# main_ver1_0.net
KiCad netlist of a schematic drawn in EAGLE
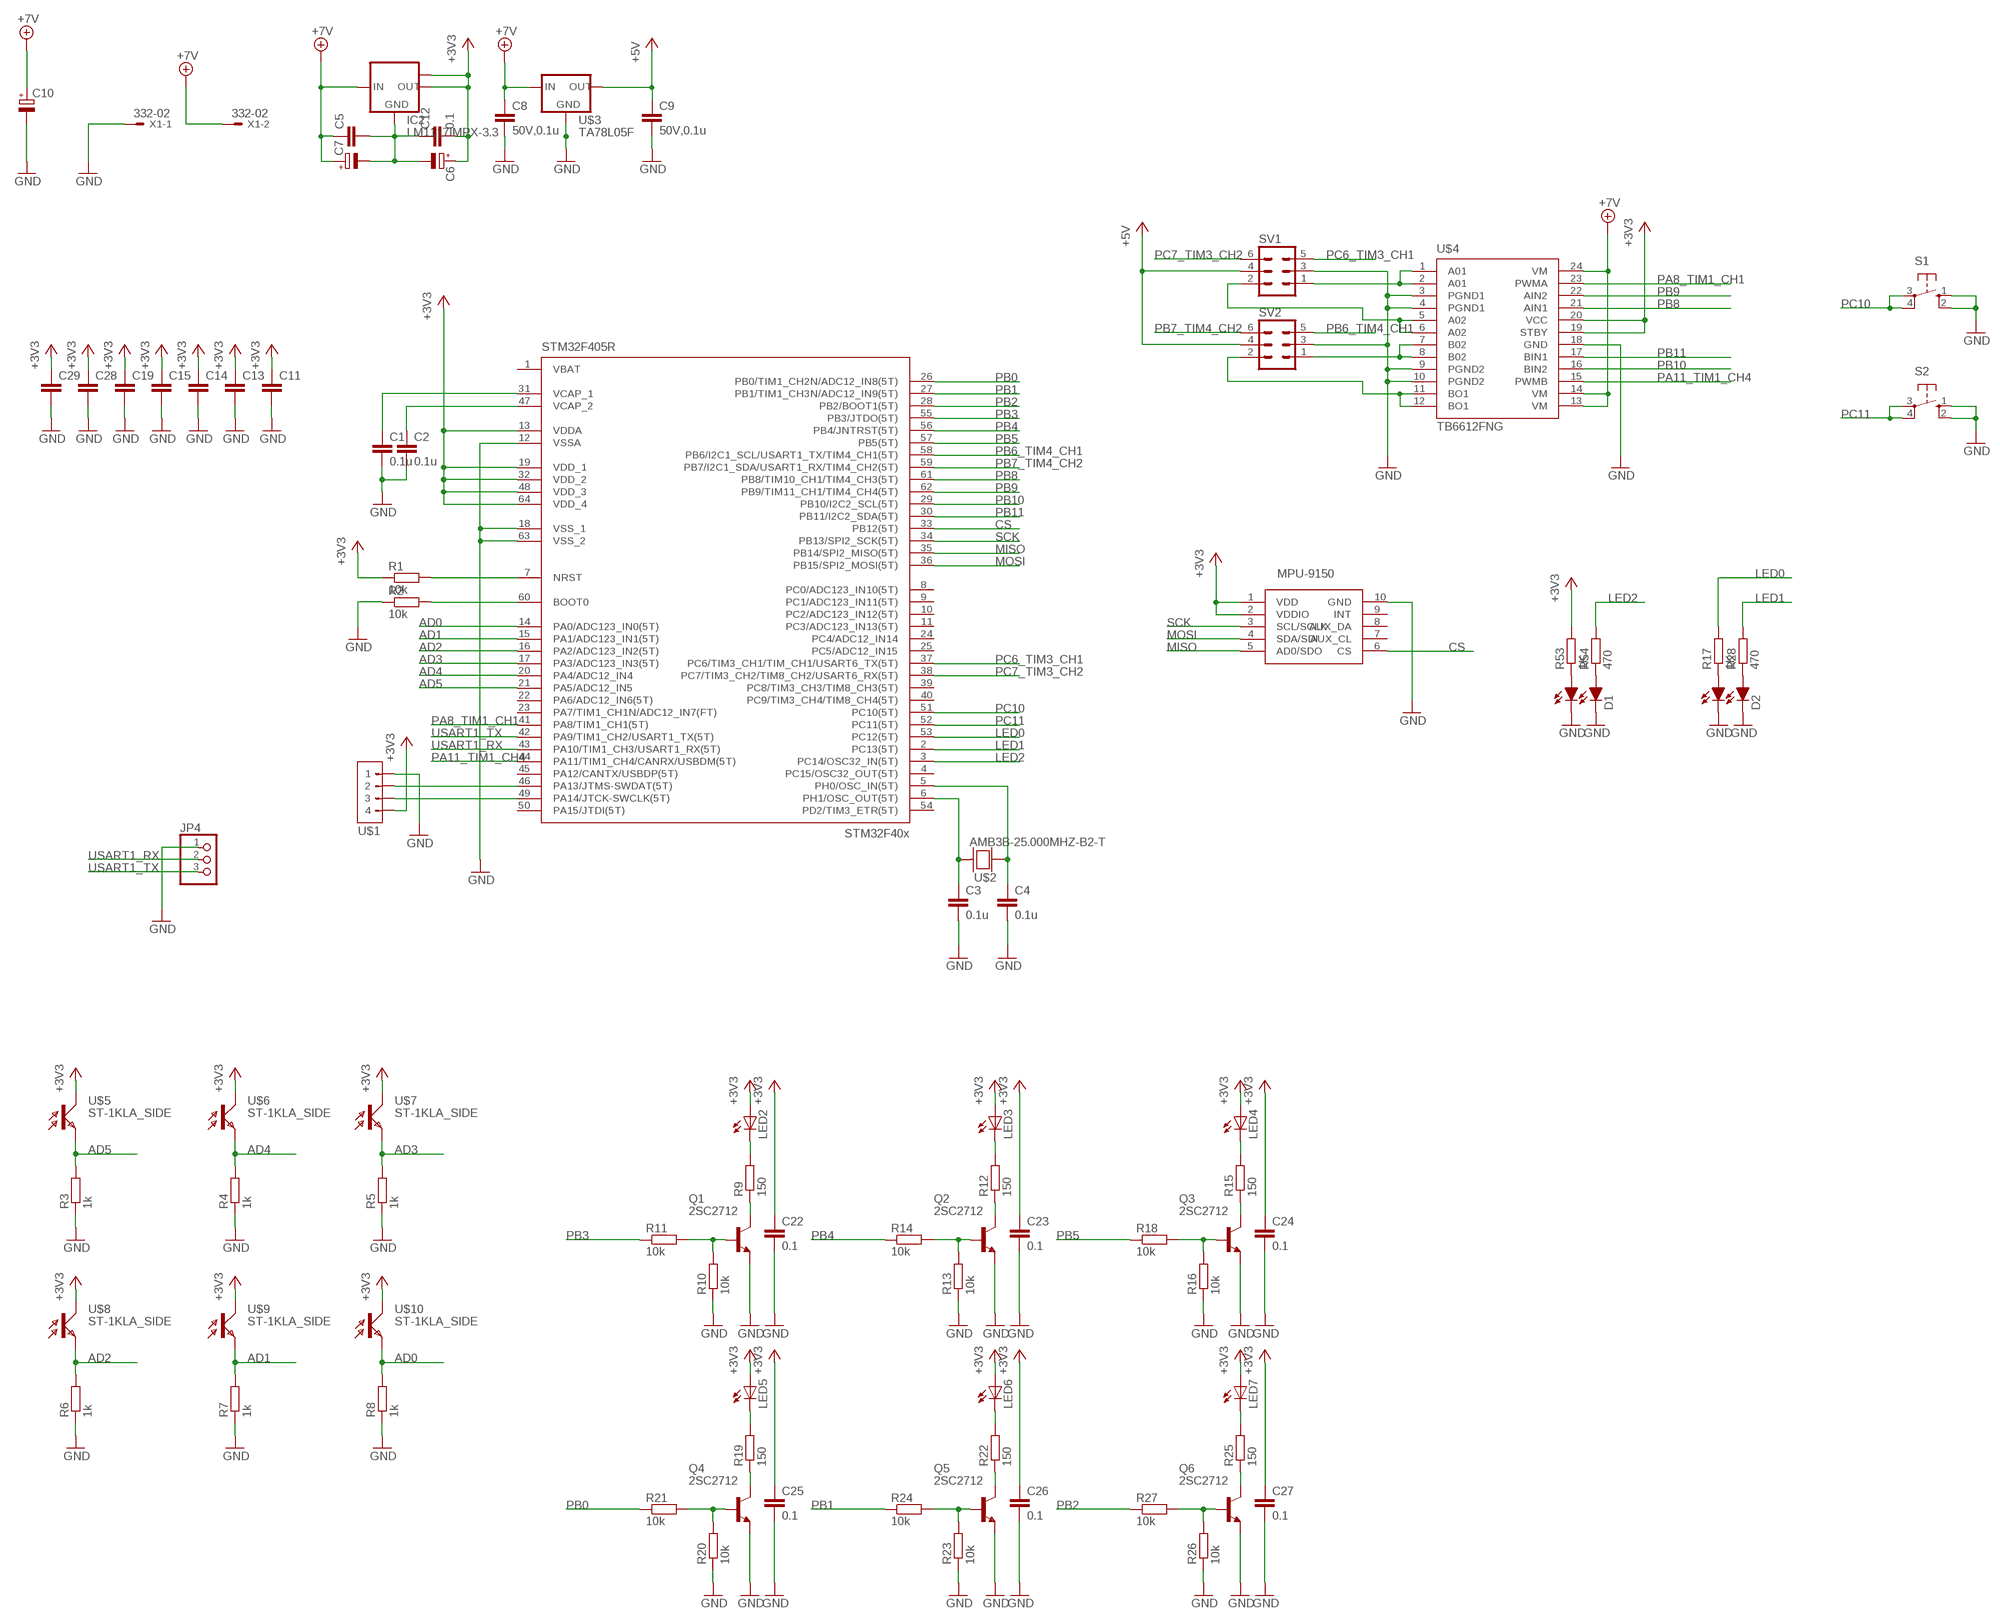
[diagram p0: schematic, sheet 1]

(export (version "E")
  (design (tool "Eeschema 10.0.6"))
  (components
    (comp (ref "C1")
      (value "0.1u")
      (footprint "eagle-import:C0603K")
      (libsource (lib "eagle-import") (part "C-EUC0603K"))
    )
    (comp (ref "C2")
      (value "0.1u")
      (footprint "eagle-import:C0603K")
      (libsource (lib "eagle-import") (part "C-EUC0603K"))
    )
    (comp (ref "C3")
      (value "0.1u")
      (footprint "eagle-import:C0603K")
      (libsource (lib "eagle-import") (part "C-EUC0603K"))
    )
    (comp (ref "C4")
      (value "0.1u")
      (footprint "eagle-import:C0603K")
      (libsource (lib "eagle-import") (part "C-EUC0603K"))
    )
    (comp (ref "C5")
      (value "C-EUC0603")
      (footprint "eagle-import:C0603")
      (libsource (lib "eagle-import") (part "C-EUC0603"))
    )
    (comp (ref "C6")
      (value "CPOL-EUSANYO_SMD_A5")
      (footprint "eagle-import:SANYO-OSCON_SMD_A5")
      (libsource (lib "eagle-import") (part "CPOL-EUSANYO_SMD_A5"))
    )
    (comp (ref "C7")
      (value "CPOL-EUSANYO_SMD_A5")
      (footprint "eagle-import:SANYO-OSCON_SMD_A5")
      (libsource (lib "eagle-import") (part "CPOL-EUSANYO_SMD_A5"))
    )
    (comp (ref "C8")
      (value "50V,0.1u")
      (footprint "eagle-import:C0603K")
      (libsource (lib "eagle-import") (part "C-EUC0603K"))
    )
    (comp (ref "C9")
      (value "50V,0.1u")
      (footprint "eagle-import:C0603K")
      (libsource (lib "eagle-import") (part "C-EUC0603K"))
    )
    (comp (ref "C10")
      (value "CPOL-EUSANYO_SMD_A5")
      (footprint "eagle-import:SANYO-OSCON_SMD_A5")
      (libsource (lib "eagle-import") (part "CPOL-EUSANYO_SMD_A5"))
    )
    (comp (ref "C11")
      (value "C-EUC0603K")
      (footprint "eagle-import:C0603K")
      (libsource (lib "eagle-import") (part "C-EUC0603K"))
    )
    (comp (ref "C12")
      (value "0.1")
      (footprint "eagle-import:C0603")
      (libsource (lib "eagle-import") (part "C-EUC0603"))
    )
    (comp (ref "C13")
      (value "C-EUC0603K")
      (footprint "eagle-import:C0603K")
      (libsource (lib "eagle-import") (part "C-EUC0603K"))
    )
    (comp (ref "C14")
      (value "C-EUC0603K")
      (footprint "eagle-import:C0603K")
      (libsource (lib "eagle-import") (part "C-EUC0603K"))
    )
    (comp (ref "C15")
      (value "C-EUC0603K")
      (footprint "eagle-import:C0603K")
      (libsource (lib "eagle-import") (part "C-EUC0603K"))
    )
    (comp (ref "C19")
      (value "C-EUC0603K")
      (footprint "eagle-import:C0603K")
      (libsource (lib "eagle-import") (part "C-EUC0603K"))
    )
    (comp (ref "C22")
      (value "0.1")
      (footprint "eagle-import:C0603")
      (libsource (lib "eagle-import") (part "C-EUC0603"))
    )
    (comp (ref "C23")
      (value "0.1")
      (footprint "eagle-import:C0603")
      (libsource (lib "eagle-import") (part "C-EUC0603"))
    )
    (comp (ref "C24")
      (value "0.1")
      (footprint "eagle-import:C0603")
      (libsource (lib "eagle-import") (part "C-EUC0603"))
    )
    (comp (ref "C25")
      (value "0.1")
      (footprint "eagle-import:C0603")
      (libsource (lib "eagle-import") (part "C-EUC0603"))
    )
    (comp (ref "C26")
      (value "0.1")
      (footprint "eagle-import:C0603")
      (libsource (lib "eagle-import") (part "C-EUC0603"))
    )
    (comp (ref "C27")
      (value "0.1")
      (footprint "eagle-import:C0603")
      (libsource (lib "eagle-import") (part "C-EUC0603"))
    )
    (comp (ref "C28")
      (value "C-EUC0603K")
      (footprint "eagle-import:C0603K")
      (libsource (lib "eagle-import") (part "C-EUC0603K"))
    )
    (comp (ref "C29")
      (value "C-EUC0603K")
      (footprint "eagle-import:C0603K")
      (libsource (lib "eagle-import") (part "C-EUC0603K"))
    )
    (comp (ref "D1")
      (value "SEC2XX4")
      (footprint "eagle-import:LED3025")
      (libsource (lib "eagle-import") (part "SEC2XX4"))
    )
    (comp (ref "D2")
      (value "SEC2XX4")
      (footprint "eagle-import:LED3025")
      (libsource (lib "eagle-import") (part "SEC2XX4"))
    )
    (comp (ref "IC2")
      (value "LM1117IMPX-3.3")
      (footprint "eagle-import:SOT223")
      (libsource (lib "eagle-import") (part "LM1117IMPX-3.3"))
    )
    (comp (ref "JP4")
      (value "PINHD-1X3/90")
      (footprint "eagle-import:1X03_90")
      (libsource (lib "eagle-import") (part "PINHD-1X3/90"))
    )
    (comp (ref "LED2")
      (value "LEDSFH480")
      (footprint "eagle-import:SFH480")
      (libsource (lib "eagle-import") (part "LEDSFH480"))
    )
    (comp (ref "LED3")
      (value "LEDSFH480")
      (footprint "eagle-import:SFH480")
      (libsource (lib "eagle-import") (part "LEDSFH480"))
    )
    (comp (ref "LED4")
      (value "LEDSFH480")
      (footprint "eagle-import:SFH480")
      (libsource (lib "eagle-import") (part "LEDSFH480"))
    )
    (comp (ref "LED5")
      (value "LEDSFH480")
      (footprint "eagle-import:SFH480")
      (libsource (lib "eagle-import") (part "LEDSFH480"))
    )
    (comp (ref "LED6")
      (value "LEDSFH480")
      (footprint "eagle-import:SFH480")
      (libsource (lib "eagle-import") (part "LEDSFH480"))
    )
    (comp (ref "LED7")
      (value "LEDSFH480")
      (footprint "eagle-import:SFH480")
      (libsource (lib "eagle-import") (part "LEDSFH480"))
    )
    (comp (ref "MPU-9250")
      (value "MPU-9250")
      (footprint "eagle-import:MPU-9250")
      (libsource (lib "eagle-import") (part "MPU-9250"))
    )
    (comp (ref "Q1")
      (value "2SC2712")
      (footprint "eagle-import:SC-59(TYPE1)")
      (libsource (lib "eagle-import") (part "2SC2712"))
    )
    (comp (ref "Q2")
      (value "2SC2712")
      (footprint "eagle-import:SC-59(TYPE1)")
      (libsource (lib "eagle-import") (part "2SC2712"))
    )
    (comp (ref "Q3")
      (value "2SC2712")
      (footprint "eagle-import:SC-59(TYPE1)")
      (libsource (lib "eagle-import") (part "2SC2712"))
    )
    (comp (ref "Q4")
      (value "2SC2712")
      (footprint "eagle-import:SC-59(TYPE1)")
      (libsource (lib "eagle-import") (part "2SC2712"))
    )
    (comp (ref "Q5")
      (value "2SC2712")
      (footprint "eagle-import:SC-59(TYPE1)")
      (libsource (lib "eagle-import") (part "2SC2712"))
    )
    (comp (ref "Q6")
      (value "2SC2712")
      (footprint "eagle-import:SC-59(TYPE1)")
      (libsource (lib "eagle-import") (part "2SC2712"))
    )
    (comp (ref "R1")
      (value "10k")
      (footprint "eagle-import:R0603")
      (libsource (lib "eagle-import") (part "R-EU_R0603"))
    )
    (comp (ref "R2")
      (value "10k")
      (footprint "eagle-import:R0603")
      (libsource (lib "eagle-import") (part "R-EU_R0603"))
    )
    (comp (ref "R3")
      (value "1k")
      (footprint "eagle-import:R0603")
      (libsource (lib "eagle-import") (part "R-EU_R0603"))
    )
    (comp (ref "R4")
      (value "1k")
      (footprint "eagle-import:R0603")
      (libsource (lib "eagle-import") (part "R-EU_R0603"))
    )
    (comp (ref "R5")
      (value "1k")
      (footprint "eagle-import:R0603")
      (libsource (lib "eagle-import") (part "R-EU_R0603"))
    )
    (comp (ref "R6")
      (value "1k")
      (footprint "eagle-import:R0603")
      (libsource (lib "eagle-import") (part "R-EU_R0603"))
    )
    (comp (ref "R7")
      (value "1k")
      (footprint "eagle-import:R0603")
      (libsource (lib "eagle-import") (part "R-EU_R0603"))
    )
    (comp (ref "R8")
      (value "1k")
      (footprint "eagle-import:R0603")
      (libsource (lib "eagle-import") (part "R-EU_R0603"))
    )
    (comp (ref "R9")
      (value "150")
      (footprint "eagle-import:R0603")
      (libsource (lib "eagle-import") (part "R-EU_R0603"))
    )
    (comp (ref "R10")
      (value "10k")
      (footprint "eagle-import:R0603")
      (libsource (lib "eagle-import") (part "R-EU_R0603"))
    )
    (comp (ref "R11")
      (value "10k")
      (footprint "eagle-import:R0603")
      (libsource (lib "eagle-import") (part "R-EU_R0603"))
    )
    (comp (ref "R12")
      (value "150")
      (footprint "eagle-import:R0603")
      (libsource (lib "eagle-import") (part "R-EU_R0603"))
    )
    (comp (ref "R13")
      (value "10k")
      (footprint "eagle-import:R0603")
      (libsource (lib "eagle-import") (part "R-EU_R0603"))
    )
    (comp (ref "R14")
      (value "10k")
      (footprint "eagle-import:R0603")
      (libsource (lib "eagle-import") (part "R-EU_R0603"))
    )
    (comp (ref "R15")
      (value "150")
      (footprint "eagle-import:R0603")
      (libsource (lib "eagle-import") (part "R-EU_R0603"))
    )
    (comp (ref "R16")
      (value "10k")
      (footprint "eagle-import:R0603")
      (libsource (lib "eagle-import") (part "R-EU_R0603"))
    )
    (comp (ref "R17")
      (value "1K")
      (footprint "eagle-import:R0603")
      (libsource (lib "eagle-import") (part "R-EU_R0603"))
    )
    (comp (ref "R18")
      (value "10k")
      (footprint "eagle-import:R0603")
      (libsource (lib "eagle-import") (part "R-EU_R0603"))
    )
    (comp (ref "R19")
      (value "150")
      (footprint "eagle-import:R0603")
      (libsource (lib "eagle-import") (part "R-EU_R0603"))
    )
    (comp (ref "R20")
      (value "10k")
      (footprint "eagle-import:R0603")
      (libsource (lib "eagle-import") (part "R-EU_R0603"))
    )
    (comp (ref "R21")
      (value "10k")
      (footprint "eagle-import:R0603")
      (libsource (lib "eagle-import") (part "R-EU_R0603"))
    )
    (comp (ref "R22")
      (value "150")
      (footprint "eagle-import:R0603")
      (libsource (lib "eagle-import") (part "R-EU_R0603"))
    )
    (comp (ref "R23")
      (value "10k")
      (footprint "eagle-import:R0603")
      (libsource (lib "eagle-import") (part "R-EU_R0603"))
    )
    (comp (ref "R24")
      (value "10k")
      (footprint "eagle-import:R0603")
      (libsource (lib "eagle-import") (part "R-EU_R0603"))
    )
    (comp (ref "R25")
      (value "150")
      (footprint "eagle-import:R0603")
      (libsource (lib "eagle-import") (part "R-EU_R0603"))
    )
    (comp (ref "R26")
      (value "10k")
      (footprint "eagle-import:R0603")
      (libsource (lib "eagle-import") (part "R-EU_R0603"))
    )
    (comp (ref "R27")
      (value "10k")
      (footprint "eagle-import:R0603")
      (libsource (lib "eagle-import") (part "R-EU_R0603"))
    )
    (comp (ref "R28")
      (value "470")
      (footprint "eagle-import:R0603")
      (libsource (lib "eagle-import") (part "R-EU_R0603"))
    )
    (comp (ref "R53")
      (value "1K")
      (footprint "eagle-import:R0603")
      (libsource (lib "eagle-import") (part "R-EU_R0603"))
    )
    (comp (ref "R54")
      (value "470")
      (footprint "eagle-import:R0603")
      (libsource (lib "eagle-import") (part "R-EU_R0603"))
    )
    (comp (ref "S1")
      (value "10-XX")
      (footprint "eagle-import:B3F-10XX")
      (fields (field (name "MPN") "B3F-1000"))
      (libsource (lib "eagle-import") (part "10-XX"))
    )
    (comp (ref "S2")
      (value "10-XX")
      (footprint "eagle-import:B3F-10XX")
      (fields (field (name "MPN") "B3F-1000"))
      (libsource (lib "eagle-import") (part "10-XX"))
    )
    (comp (ref "STM32F405R")
      (value "STM32F405R")
      (footprint "eagle-import:TQFP64")
      (libsource (lib "eagle-import") (part "STM32F405R"))
    )
    (comp (ref "SV1")
      (value "ML6")
      (footprint "eagle-import:ML6")
      (libsource (lib "eagle-import") (part "ML6"))
    )
    (comp (ref "SV2")
      (value "ML6")
      (footprint "eagle-import:ML6")
      (libsource (lib "eagle-import") (part "ML6"))
    )
    (comp (ref "U$1")
      (value "TOP_TYPE_4PIN")
      (footprint "eagle-import:TOP_TYPE_4PIN")
      (libsource (lib "eagle-import") (part "TOP_TYPE_4PIN"))
    )
    (comp (ref "U$2")
      (value "AMB3B-25.000MHZ-B2-T")
      (footprint "eagle-import:4LCC")
      (libsource (lib "eagle-import") (part "AMB3B-25.000MHZ-B2-T"))
    )
    (comp (ref "U$3")
      (value "TA78L05F")
      (footprint "eagle-import:SOT89")
      (libsource (lib "eagle-import") (part "TA78L05F"))
    )
    (comp (ref "U$4")
      (value "TB6612FNG")
      (footprint "eagle-import:SSOP24")
      (libsource (lib "eagle-import") (part "TB6612FNG"))
    )
    (comp (ref "U$5")
      (value "ST-1KLA_SIDE")
      (footprint "eagle-import:TO18-SIDE")
      (libsource (lib "eagle-import") (part "ST-1KLA_SIDE"))
    )
    (comp (ref "U$6")
      (value "ST-1KLA_SIDE")
      (footprint "eagle-import:TO18-SIDE")
      (libsource (lib "eagle-import") (part "ST-1KLA_SIDE"))
    )
    (comp (ref "U$7")
      (value "ST-1KLA_SIDE")
      (footprint "eagle-import:TO18-SIDE")
      (libsource (lib "eagle-import") (part "ST-1KLA_SIDE"))
    )
    (comp (ref "U$8")
      (value "ST-1KLA_SIDE")
      (footprint "eagle-import:TO18-SIDE")
      (libsource (lib "eagle-import") (part "ST-1KLA_SIDE"))
    )
    (comp (ref "U$9")
      (value "ST-1KLA_SIDE")
      (footprint "eagle-import:TO18-SIDE")
      (libsource (lib "eagle-import") (part "ST-1KLA_SIDE"))
    )
    (comp (ref "U$10")
      (value "ST-1KLA_SIDE")
      (footprint "eagle-import:TO18-SIDE")
      (libsource (lib "eagle-import") (part "ST-1KLA_SIDE"))
    )
    (comp (ref "X1")
      (value "332-02")
      (footprint "eagle-import:332-02")
      (libsource (lib "eagle-import") (part "332-02"))
    )
  )
  (nets
    (net (code "1") (name "+3V3") (class "Default")
      (node (ref "C11") (pin "1") (pinfunction "1_1") (pintype "passive"))
      (node (ref "C12") (pin "2") (pinfunction "2_2") (pintype "passive"))
      (node (ref "C13") (pin "1") (pinfunction "1_1") (pintype "passive"))
      (node (ref "C14") (pin "1") (pinfunction "1_1") (pintype "passive"))
      (node (ref "C15") (pin "1") (pinfunction "1_1") (pintype "passive"))
      (node (ref "C19") (pin "1") (pinfunction "1_1") (pintype "passive"))
      (node (ref "C22") (pin "1") (pinfunction "1_1") (pintype "passive"))
      (node (ref "C23") (pin "1") (pinfunction "1_1") (pintype "passive"))
      (node (ref "C24") (pin "1") (pinfunction "1_1") (pintype "passive"))
      (node (ref "C25") (pin "1") (pinfunction "1_1") (pintype "passive"))
      (node (ref "C26") (pin "1") (pinfunction "1_1") (pintype "passive"))
      (node (ref "C27") (pin "1") (pinfunction "1_1") (pintype "passive"))
      (node (ref "C28") (pin "1") (pinfunction "1_1") (pintype "passive"))
      (node (ref "C29") (pin "1") (pinfunction "1_1") (pintype "passive"))
      (node (ref "C6") (pin "+") (pinfunction "+_+") (pintype "passive"))
      (node (ref "IC2") (pin "2") (pinfunction "OUT_2") (pintype "passive"))
      (node (ref "IC2") (pin "TAB") (pinfunction "OUT1_TAB") (pintype "passive"))
      (node (ref "LED2") (pin "A") (pinfunction "A_A") (pintype "passive"))
      (node (ref "LED3") (pin "A") (pinfunction "A_A") (pintype "passive"))
      (node (ref "LED4") (pin "A") (pinfunction "A_A") (pintype "passive"))
      (node (ref "LED5") (pin "A") (pinfunction "A_A") (pintype "passive"))
      (node (ref "LED6") (pin "A") (pinfunction "A_A") (pintype "passive"))
      (node (ref "LED7") (pin "A") (pinfunction "A_A") (pintype "passive"))
      (node (ref "MPU-9250") (pin "1") (pinfunction "VDD_1") (pintype "bidirectional"))
      (node (ref "MPU-9250") (pin "2") (pinfunction "VDDIO_2") (pintype "bidirectional"))
      (node (ref "R1") (pin "1") (pinfunction "1_1") (pintype "passive"))
      (node (ref "R53") (pin "2") (pinfunction "2_2") (pintype "passive"))
      (node (ref "STM32F405R") (pin "13") (pinfunction "VDDA_13") (pintype "bidirectional"))
      (node (ref "STM32F405R") (pin "19") (pinfunction "VDD_1_19") (pintype "bidirectional"))
      (node (ref "STM32F405R") (pin "32") (pinfunction "VDD_2_32") (pintype "bidirectional"))
      (node (ref "STM32F405R") (pin "48") (pinfunction "VDD_3_48") (pintype "bidirectional"))
      (node (ref "STM32F405R") (pin "64") (pinfunction "VDD_4_64") (pintype "bidirectional"))
      (node (ref "U$1") (pin "4") (pinfunction "4_4") (pintype "passive"))
      (node (ref "U$10") (pin "P$2") (pinfunction "C_P$2") (pintype "passive"))
      (node (ref "U$4") (pin "19") (pinfunction "STBY_19") (pintype "bidirectional"))
      (node (ref "U$4") (pin "20") (pinfunction "VCC_20") (pintype "bidirectional"))
      (node (ref "U$5") (pin "P$2") (pinfunction "C_P$2") (pintype "passive"))
      (node (ref "U$6") (pin "P$2") (pinfunction "C_P$2") (pintype "passive"))
      (node (ref "U$7") (pin "P$2") (pinfunction "C_P$2") (pintype "passive"))
      (node (ref "U$8") (pin "P$2") (pinfunction "C_P$2") (pintype "passive"))
      (node (ref "U$9") (pin "P$2") (pinfunction "C_P$2") (pintype "passive"))
    )
    (net (code "2") (name "+5V") (class "Default")
      (node (ref "C9") (pin "1") (pinfunction "1_1") (pintype "passive"))
      (node (ref "SV1") (pin "4") (pinfunction "4_4") (pintype "passive"))
      (node (ref "SV2") (pin "4") (pinfunction "4_4") (pintype "passive"))
      (node (ref "U$3") (pin "1") (pinfunction "OUT_1") (pintype "passive"))
    )
    (net (code "3") (name "+7V") (class "Default")
      (node (ref "C10") (pin "+") (pinfunction "+_+") (pintype "passive"))
      (node (ref "C5") (pin "1") (pinfunction "1_1") (pintype "passive"))
      (node (ref "C7") (pin "+") (pinfunction "+_+") (pintype "passive"))
      (node (ref "C8") (pin "1") (pinfunction "1_1") (pintype "passive"))
      (node (ref "IC2") (pin "3") (pinfunction "IN_3") (pintype "input"))
      (node (ref "U$3") (pin "3") (pinfunction "IN_3") (pintype "input"))
      (node (ref "U$4") (pin "13") (pinfunction "VM_13") (pintype "bidirectional"))
      (node (ref "U$4") (pin "14") (pinfunction "VM_14") (pintype "bidirectional"))
      (node (ref "U$4") (pin "24") (pinfunction "VM_24") (pintype "bidirectional"))
      (node (ref "X1") (pin "2") (pinfunction "S_2") (pintype "passive"))
    )
    (net (code "4") (name "/AD0") (class "Default")
      (node (ref "R8") (pin "2") (pinfunction "2_2") (pintype "passive"))
      (node (ref "STM32F405R") (pin "14") (pinfunction "PA0/ADC123_IN0(5T)_14") (pintype "bidirectional"))
      (node (ref "U$10") (pin "P$1") (pinfunction "E_P$1") (pintype "passive"))
    )
    (net (code "5") (name "/AD1") (class "Default")
      (node (ref "R7") (pin "2") (pinfunction "2_2") (pintype "passive"))
      (node (ref "STM32F405R") (pin "15") (pinfunction "PA1/ADC123_IN1(5T)_15") (pintype "bidirectional"))
      (node (ref "U$9") (pin "P$1") (pinfunction "E_P$1") (pintype "passive"))
    )
    (net (code "6") (name "/AD2") (class "Default")
      (node (ref "R6") (pin "2") (pinfunction "2_2") (pintype "passive"))
      (node (ref "STM32F405R") (pin "16") (pinfunction "PA2/ADC123_IN2(5T)_16") (pintype "bidirectional"))
      (node (ref "U$8") (pin "P$1") (pinfunction "E_P$1") (pintype "passive"))
    )
    (net (code "7") (name "/AD3") (class "Default")
      (node (ref "R5") (pin "2") (pinfunction "2_2") (pintype "passive"))
      (node (ref "STM32F405R") (pin "17") (pinfunction "PA3/ADC123_IN3(5T)_17") (pintype "bidirectional"))
      (node (ref "U$7") (pin "P$1") (pinfunction "E_P$1") (pintype "passive"))
    )
    (net (code "8") (name "/AD4") (class "Default")
      (node (ref "R4") (pin "2") (pinfunction "2_2") (pintype "passive"))
      (node (ref "STM32F405R") (pin "20") (pinfunction "PA4/ADC12_IN4_20") (pintype "bidirectional"))
      (node (ref "U$6") (pin "P$1") (pinfunction "E_P$1") (pintype "passive"))
    )
    (net (code "9") (name "/AD5") (class "Default")
      (node (ref "R3") (pin "2") (pinfunction "2_2") (pintype "passive"))
      (node (ref "STM32F405R") (pin "21") (pinfunction "PA5/ADC12_IN5_21") (pintype "bidirectional"))
      (node (ref "U$5") (pin "P$1") (pinfunction "E_P$1") (pintype "passive"))
    )
    (net (code "10") (name "/CS") (class "Default")
      (node (ref "MPU-9250") (pin "6") (pinfunction "CS_6") (pintype "bidirectional"))
      (node (ref "STM32F405R") (pin "33") (pinfunction "PB12(5T)_33") (pintype "bidirectional"))
    )
    (net (code "11") (name "/LED0") (class "Default")
      (node (ref "R17") (pin "2") (pinfunction "2_2") (pintype "passive"))
      (node (ref "STM32F405R") (pin "53") (pinfunction "PC12(5T)_53") (pintype "bidirectional"))
    )
    (net (code "12") (name "/LED1") (class "Default")
      (node (ref "R28") (pin "2") (pinfunction "2_2") (pintype "passive"))
      (node (ref "STM32F405R") (pin "2") (pinfunction "PC13(5T)_2") (pintype "bidirectional"))
    )
    (net (code "13") (name "/LED2") (class "Default")
      (node (ref "R54") (pin "2") (pinfunction "2_2") (pintype "passive"))
      (node (ref "STM32F405R") (pin "3") (pinfunction "PC14/OSC32_IN(5T)_3") (pintype "bidirectional"))
    )
    (net (code "14") (name "/MISO") (class "Default")
      (node (ref "MPU-9250") (pin "5") (pinfunction "AD0/SDO_5") (pintype "bidirectional"))
      (node (ref "STM32F405R") (pin "35") (pinfunction "PB14/SPI2_MISO(5T)_35") (pintype "bidirectional"))
    )
    (net (code "15") (name "/MOSI") (class "Default")
      (node (ref "MPU-9250") (pin "4") (pinfunction "SDA/SDI_4") (pintype "bidirectional"))
      (node (ref "STM32F405R") (pin "36") (pinfunction "PB15/SPI2_MOSI(5T)_36") (pintype "bidirectional"))
    )
    (net (code "16") (name "/PA8_TIM1_CH1") (class "Default")
      (node (ref "STM32F405R") (pin "41") (pinfunction "PA8/TIM1_CH1(5T)_41") (pintype "bidirectional"))
      (node (ref "U$4") (pin "23") (pinfunction "PWMA_23") (pintype "bidirectional"))
    )
    (net (code "17") (name "/PA11_TIM1_CH4") (class "Default")
      (node (ref "STM32F405R") (pin "44") (pinfunction "PA11/TIM1_CH4/CANRX/USBDM(5T)_44") (pintype "bidirectional"))
      (node (ref "U$4") (pin "15") (pinfunction "PWMB_15") (pintype "bidirectional"))
    )
    (net (code "18") (name "/PB0") (class "Default")
      (node (ref "R21") (pin "1") (pinfunction "1_1") (pintype "passive"))
      (node (ref "STM32F405R") (pin "26") (pinfunction "PB0/TIM1_CH2N/ADC12_IN8(5T)_26") (pintype "bidirectional"))
    )
    (net (code "19") (name "/PB1") (class "Default")
      (node (ref "R24") (pin "1") (pinfunction "1_1") (pintype "passive"))
      (node (ref "STM32F405R") (pin "27") (pinfunction "PB1/TIM1_CH3N/ADC12_IN9(5T)_27") (pintype "bidirectional"))
    )
    (net (code "20") (name "/PB2") (class "Default")
      (node (ref "R27") (pin "1") (pinfunction "1_1") (pintype "passive"))
      (node (ref "STM32F405R") (pin "28") (pinfunction "PB2/BOOT1(5T)_28") (pintype "bidirectional"))
    )
    (net (code "21") (name "/PB3") (class "Default")
      (node (ref "R11") (pin "1") (pinfunction "1_1") (pintype "passive"))
      (node (ref "STM32F405R") (pin "55") (pinfunction "PB3/JTDO(5T)_55") (pintype "bidirectional"))
    )
    (net (code "22") (name "/PB4") (class "Default")
      (node (ref "R14") (pin "1") (pinfunction "1_1") (pintype "passive"))
      (node (ref "STM32F405R") (pin "56") (pinfunction "PB4/JNTRST(5T)_56") (pintype "bidirectional"))
    )
    (net (code "23") (name "/PB5") (class "Default")
      (node (ref "R18") (pin "1") (pinfunction "1_1") (pintype "passive"))
      (node (ref "STM32F405R") (pin "57") (pinfunction "PB5(5T)_57") (pintype "bidirectional"))
    )
    (net (code "24") (name "/PB6_TIM4_CH1") (class "Default")
      (node (ref "STM32F405R") (pin "58") (pinfunction "PB6/I2C1_SCL/USART1_TX/TIM4_CH1(5T)_58") (pintype "bidirectional"))
      (node (ref "SV2") (pin "5") (pinfunction "5_5") (pintype "passive"))
    )
    (net (code "25") (name "/PB7_TIM4_CH2") (class "Default")
      (node (ref "STM32F405R") (pin "59") (pinfunction "PB7/I2C1_SDA/USART1_RX/TIM4_CH2(5T)_59") (pintype "bidirectional"))
      (node (ref "SV2") (pin "6") (pinfunction "6_6") (pintype "passive"))
    )
    (net (code "26") (name "/PB8") (class "Default")
      (node (ref "STM32F405R") (pin "61") (pinfunction "PB8/TIM10_CH1/TIM4_CH3(5T)_61") (pintype "bidirectional"))
      (node (ref "U$4") (pin "21") (pinfunction "AIN1_21") (pintype "bidirectional"))
    )
    (net (code "27") (name "/PB9") (class "Default")
      (node (ref "STM32F405R") (pin "62") (pinfunction "PB9/TIM11_CH1/TIM4_CH4(5T)_62") (pintype "bidirectional"))
      (node (ref "U$4") (pin "22") (pinfunction "AIN2_22") (pintype "bidirectional"))
    )
    (net (code "28") (name "/PB10") (class "Default")
      (node (ref "STM32F405R") (pin "29") (pinfunction "PB10/I2C2_SCL(5T)_29") (pintype "bidirectional"))
      (node (ref "U$4") (pin "16") (pinfunction "BIN2_16") (pintype "bidirectional"))
    )
    (net (code "29") (name "/PB11") (class "Default")
      (node (ref "STM32F405R") (pin "30") (pinfunction "PB11/I2C2_SDA(5T)_30") (pintype "bidirectional"))
      (node (ref "U$4") (pin "17") (pinfunction "BIN1_17") (pintype "bidirectional"))
    )
    (net (code "30") (name "/PC6_TIM3_CH1") (class "Default")
      (node (ref "STM32F405R") (pin "37") (pinfunction "PC6/TIM3_CH1/TIM_CH1/USART6_TX(5T)_37") (pintype "bidirectional"))
      (node (ref "SV1") (pin "5") (pinfunction "5_5") (pintype "passive"))
    )
    (net (code "31") (name "/PC7_TIM3_CH2") (class "Default")
      (node (ref "STM32F405R") (pin "38") (pinfunction "PC7/TIM3_CH2/TIM8_CH2/USART6_RX(5T)_38") (pintype "bidirectional"))
      (node (ref "SV1") (pin "6") (pinfunction "6_6") (pintype "passive"))
    )
    (net (code "32") (name "/PC10") (class "Default")
      (node (ref "S1") (pin "3") (pinfunction "P_3") (pintype "passive"))
      (node (ref "S1") (pin "4") (pinfunction "P1_4") (pintype "passive"))
      (node (ref "STM32F405R") (pin "51") (pinfunction "PC10(5T)_51") (pintype "bidirectional"))
    )
    (net (code "33") (name "/PC11") (class "Default")
      (node (ref "S2") (pin "3") (pinfunction "P_3") (pintype "passive"))
      (node (ref "S2") (pin "4") (pinfunction "P1_4") (pintype "passive"))
      (node (ref "STM32F405R") (pin "52") (pinfunction "PC11(5T)_52") (pintype "bidirectional"))
    )
    (net (code "34") (name "/SCK") (class "Default")
      (node (ref "MPU-9250") (pin "3") (pinfunction "SCL/SCLK_3") (pintype "bidirectional"))
      (node (ref "STM32F405R") (pin "34") (pinfunction "PB13/SPI2_SCK(5T)_34") (pintype "bidirectional"))
    )
    (net (code "35") (name "/USART1_RX") (class "Default")
      (node (ref "JP4") (pin "2") (pinfunction "2_2") (pintype "passive"))
      (node (ref "STM32F405R") (pin "43") (pinfunction "PA10/TIM1_CH3/USART1_RX(5T)_43") (pintype "bidirectional"))
    )
    (net (code "36") (name "/USART1_TX") (class "Default")
      (node (ref "JP4") (pin "3") (pinfunction "3_3") (pintype "passive"))
      (node (ref "STM32F405R") (pin "42") (pinfunction "PA9/TIM1_CH2/USART1_TX(5T)_42") (pintype "bidirectional"))
    )
    (net (code "37") (name "GND") (class "Default")
      (node (ref "C1") (pin "2") (pinfunction "2_2") (pintype "passive"))
      (node (ref "C10") (pin "-") (pinfunction "-_-") (pintype "passive"))
      (node (ref "C11") (pin "2") (pinfunction "2_2") (pintype "passive"))
      (node (ref "C12") (pin "1") (pinfunction "1_1") (pintype "passive"))
      (node (ref "C13") (pin "2") (pinfunction "2_2") (pintype "passive"))
      (node (ref "C14") (pin "2") (pinfunction "2_2") (pintype "passive"))
      (node (ref "C15") (pin "2") (pinfunction "2_2") (pintype "passive"))
      (node (ref "C19") (pin "2") (pinfunction "2_2") (pintype "passive"))
      (node (ref "C2") (pin "2") (pinfunction "2_2") (pintype "passive"))
      (node (ref "C22") (pin "2") (pinfunction "2_2") (pintype "passive"))
      (node (ref "C23") (pin "2") (pinfunction "2_2") (pintype "passive"))
      (node (ref "C24") (pin "2") (pinfunction "2_2") (pintype "passive"))
      (node (ref "C25") (pin "2") (pinfunction "2_2") (pintype "passive"))
      (node (ref "C26") (pin "2") (pinfunction "2_2") (pintype "passive"))
      (node (ref "C27") (pin "2") (pinfunction "2_2") (pintype "passive"))
      (node (ref "C28") (pin "2") (pinfunction "2_2") (pintype "passive"))
      (node (ref "C29") (pin "2") (pinfunction "2_2") (pintype "passive"))
      (node (ref "C3") (pin "2") (pinfunction "2_2") (pintype "passive"))
      (node (ref "C4") (pin "2") (pinfunction "2_2") (pintype "passive"))
      (node (ref "C5") (pin "2") (pinfunction "2_2") (pintype "passive"))
      (node (ref "C6") (pin "-") (pinfunction "-_-") (pintype "passive"))
      (node (ref "C7") (pin "-") (pinfunction "-_-") (pintype "passive"))
      (node (ref "C8") (pin "2") (pinfunction "2_2") (pintype "passive"))
      (node (ref "C9") (pin "2") (pinfunction "2_2") (pintype "passive"))
      (node (ref "D1") (pin "1") (pinfunction "C0_1") (pintype "passive"))
      (node (ref "D1") (pin "2") (pinfunction "C1_2") (pintype "passive"))
      (node (ref "D2") (pin "1") (pinfunction "C0_1") (pintype "passive"))
      (node (ref "D2") (pin "2") (pinfunction "C1_2") (pintype "passive"))
      (node (ref "IC2") (pin "1") (pinfunction "GND_1") (pintype "input"))
      (node (ref "JP4") (pin "1") (pinfunction "1_1") (pintype "passive"))
      (node (ref "MPU-9250") (pin "10") (pinfunction "GND_10") (pintype "bidirectional"))
      (node (ref "Q1") (pin "E") (pinfunction "E_E") (pintype "passive"))
      (node (ref "Q2") (pin "E") (pinfunction "E_E") (pintype "passive"))
      (node (ref "Q3") (pin "E") (pinfunction "E_E") (pintype "passive"))
      (node (ref "Q4") (pin "E") (pinfunction "E_E") (pintype "passive"))
      (node (ref "Q5") (pin "E") (pinfunction "E_E") (pintype "passive"))
      (node (ref "Q6") (pin "E") (pinfunction "E_E") (pintype "passive"))
      (node (ref "R10") (pin "1") (pinfunction "1_1") (pintype "passive"))
      (node (ref "R13") (pin "1") (pinfunction "1_1") (pintype "passive"))
      (node (ref "R16") (pin "1") (pinfunction "1_1") (pintype "passive"))
      (node (ref "R2") (pin "1") (pinfunction "1_1") (pintype "passive"))
      (node (ref "R20") (pin "1") (pinfunction "1_1") (pintype "passive"))
      (node (ref "R23") (pin "1") (pinfunction "1_1") (pintype "passive"))
      (node (ref "R26") (pin "1") (pinfunction "1_1") (pintype "passive"))
      (node (ref "R3") (pin "1") (pinfunction "1_1") (pintype "passive"))
      (node (ref "R4") (pin "1") (pinfunction "1_1") (pintype "passive"))
      (node (ref "R5") (pin "1") (pinfunction "1_1") (pintype "passive"))
      (node (ref "R6") (pin "1") (pinfunction "1_1") (pintype "passive"))
      (node (ref "R7") (pin "1") (pinfunction "1_1") (pintype "passive"))
      (node (ref "R8") (pin "1") (pinfunction "1_1") (pintype "passive"))
      (node (ref "S1") (pin "1") (pinfunction "S_1") (pintype "passive"))
      (node (ref "S1") (pin "2") (pinfunction "S1_2") (pintype "passive"))
      (node (ref "S2") (pin "1") (pinfunction "S_1") (pintype "passive"))
      (node (ref "S2") (pin "2") (pinfunction "S1_2") (pintype "passive"))
      (node (ref "STM32F405R") (pin "12") (pinfunction "VSSA_12") (pintype "bidirectional"))
      (node (ref "STM32F405R") (pin "18") (pinfunction "VSS_1_18") (pintype "bidirectional"))
      (node (ref "STM32F405R") (pin "63") (pinfunction "VSS_2_63") (pintype "bidirectional"))
      (node (ref "SV1") (pin "3") (pinfunction "3_3") (pintype "passive"))
      (node (ref "SV2") (pin "3") (pinfunction "3_3") (pintype "passive"))
      (node (ref "U$1") (pin "1") (pinfunction "1_1") (pintype "passive"))
      (node (ref "U$3") (pin "2") (pinfunction "GND_2") (pintype "input"))
      (node (ref "U$3") (pin "2@1") (pinfunction "GND1_2@1") (pintype "input"))
      (node (ref "U$4") (pin "10") (pinfunction "PGND2_10") (pintype "bidirectional"))
      (node (ref "U$4") (pin "18") (pinfunction "GND_18") (pintype "bidirectional"))
      (node (ref "U$4") (pin "3") (pinfunction "PGND1_3") (pintype "bidirectional"))
      (node (ref "U$4") (pin "4") (pinfunction "PGND1_4") (pintype "bidirectional"))
      (node (ref "U$4") (pin "9") (pinfunction "PGND2_9") (pintype "bidirectional"))
      (node (ref "X1") (pin "1") (pinfunction "S_1") (pintype "passive"))
    )
    (net (code "38") (name "Net-(D1-A0)") (class "Default")
      (node (ref "D1") (pin "4") (pinfunction "A0_4") (pintype "passive"))
      (node (ref "R54") (pin "1") (pinfunction "1_1") (pintype "passive"))
    )
    (net (code "39") (name "Net-(D1-A1)") (class "Default")
      (node (ref "D1") (pin "3") (pinfunction "A1_3") (pintype "passive"))
      (node (ref "R53") (pin "1") (pinfunction "1_1") (pintype "passive"))
    )
    (net (code "40") (name "Net-(D2-A0)") (class "Default")
      (node (ref "D2") (pin "4") (pinfunction "A0_4") (pintype "passive"))
      (node (ref "R28") (pin "1") (pinfunction "1_1") (pintype "passive"))
    )
    (net (code "41") (name "Net-(D2-A1)") (class "Default")
      (node (ref "D2") (pin "3") (pinfunction "A1_3") (pintype "passive"))
      (node (ref "R17") (pin "1") (pinfunction "1_1") (pintype "passive"))
    )
    (net (code "42") (name "Net-(LED2-C)") (class "Default")
      (node (ref "LED2") (pin "K") (pinfunction "C_K") (pintype "passive"))
      (node (ref "R9") (pin "2") (pinfunction "2_2") (pintype "passive"))
    )
    (net (code "43") (name "Net-(LED3-C)") (class "Default")
      (node (ref "LED3") (pin "K") (pinfunction "C_K") (pintype "passive"))
      (node (ref "R12") (pin "2") (pinfunction "2_2") (pintype "passive"))
    )
    (net (code "44") (name "Net-(LED4-C)") (class "Default")
      (node (ref "LED4") (pin "K") (pinfunction "C_K") (pintype "passive"))
      (node (ref "R15") (pin "2") (pinfunction "2_2") (pintype "passive"))
    )
    (net (code "45") (name "Net-(LED5-C)") (class "Default")
      (node (ref "LED5") (pin "K") (pinfunction "C_K") (pintype "passive"))
      (node (ref "R19") (pin "2") (pinfunction "2_2") (pintype "passive"))
    )
    (net (code "46") (name "Net-(LED6-C)") (class "Default")
      (node (ref "LED6") (pin "K") (pinfunction "C_K") (pintype "passive"))
      (node (ref "R22") (pin "2") (pinfunction "2_2") (pintype "passive"))
    )
    (net (code "47") (name "Net-(LED7-C)") (class "Default")
      (node (ref "LED7") (pin "K") (pinfunction "C_K") (pintype "passive"))
      (node (ref "R25") (pin "2") (pinfunction "2_2") (pintype "passive"))
    )
    (net (code "48") (name "Net-(Q1-PadB)") (class "Default")
      (node (ref "Q1") (pin "B") (pinfunction "B_B") (pintype "passive"))
      (node (ref "R10") (pin "2") (pinfunction "2_2") (pintype "passive"))
      (node (ref "R11") (pin "2") (pinfunction "2_2") (pintype "passive"))
    )
    (net (code "49") (name "Net-(Q1-PadC)") (class "Default")
      (node (ref "Q1") (pin "C") (pinfunction "C_C") (pintype "passive"))
      (node (ref "R9") (pin "1") (pinfunction "1_1") (pintype "passive"))
    )
    (net (code "50") (name "Net-(Q2-PadB)") (class "Default")
      (node (ref "Q2") (pin "B") (pinfunction "B_B") (pintype "passive"))
      (node (ref "R13") (pin "2") (pinfunction "2_2") (pintype "passive"))
      (node (ref "R14") (pin "2") (pinfunction "2_2") (pintype "passive"))
    )
    (net (code "51") (name "Net-(Q2-PadC)") (class "Default")
      (node (ref "Q2") (pin "C") (pinfunction "C_C") (pintype "passive"))
      (node (ref "R12") (pin "1") (pinfunction "1_1") (pintype "passive"))
    )
    (net (code "52") (name "Net-(Q3-PadB)") (class "Default")
      (node (ref "Q3") (pin "B") (pinfunction "B_B") (pintype "passive"))
      (node (ref "R16") (pin "2") (pinfunction "2_2") (pintype "passive"))
      (node (ref "R18") (pin "2") (pinfunction "2_2") (pintype "passive"))
    )
    (net (code "53") (name "Net-(Q3-PadC)") (class "Default")
      (node (ref "Q3") (pin "C") (pinfunction "C_C") (pintype "passive"))
      (node (ref "R15") (pin "1") (pinfunction "1_1") (pintype "passive"))
    )
    (net (code "54") (name "Net-(Q4-PadB)") (class "Default")
      (node (ref "Q4") (pin "B") (pinfunction "B_B") (pintype "passive"))
      (node (ref "R20") (pin "2") (pinfunction "2_2") (pintype "passive"))
      (node (ref "R21") (pin "2") (pinfunction "2_2") (pintype "passive"))
    )
    (net (code "55") (name "Net-(Q4-PadC)") (class "Default")
      (node (ref "Q4") (pin "C") (pinfunction "C_C") (pintype "passive"))
      (node (ref "R19") (pin "1") (pinfunction "1_1") (pintype "passive"))
    )
    (net (code "56") (name "Net-(Q5-PadB)") (class "Default")
      (node (ref "Q5") (pin "B") (pinfunction "B_B") (pintype "passive"))
      (node (ref "R23") (pin "2") (pinfunction "2_2") (pintype "passive"))
      (node (ref "R24") (pin "2") (pinfunction "2_2") (pintype "passive"))
    )
    (net (code "57") (name "Net-(Q5-PadC)") (class "Default")
      (node (ref "Q5") (pin "C") (pinfunction "C_C") (pintype "passive"))
      (node (ref "R22") (pin "1") (pinfunction "1_1") (pintype "passive"))
    )
    (net (code "58") (name "Net-(Q6-PadB)") (class "Default")
      (node (ref "Q6") (pin "B") (pinfunction "B_B") (pintype "passive"))
      (node (ref "R26") (pin "2") (pinfunction "2_2") (pintype "passive"))
      (node (ref "R27") (pin "2") (pinfunction "2_2") (pintype "passive"))
    )
    (net (code "59") (name "Net-(Q6-PadC)") (class "Default")
      (node (ref "Q6") (pin "C") (pinfunction "C_C") (pintype "passive"))
      (node (ref "R25") (pin "1") (pinfunction "1_1") (pintype "passive"))
    )
    (net (code "60") (name "Net-(STM32F405R-BOOT0)") (class "Default")
      (node (ref "R2") (pin "2") (pinfunction "2_2") (pintype "passive"))
      (node (ref "STM32F405R") (pin "60") (pinfunction "BOOT0_60") (pintype "bidirectional"))
    )
    (net (code "61") (name "Net-(STM32F405R-NRST)") (class "Default")
      (node (ref "R1") (pin "2") (pinfunction "2_2") (pintype "passive"))
      (node (ref "STM32F405R") (pin "7") (pinfunction "NRST_7") (pintype "bidirectional"))
    )
    (net (code "62") (name "Net-(STM32F405R-PA13{slash}JTMS-SWDAT(5T))") (class "Default")
      (node (ref "STM32F405R") (pin "46") (pinfunction "PA13/JTMS-SWDAT(5T)_46") (pintype "bidirectional"))
      (node (ref "U$1") (pin "2") (pinfunction "2_2") (pintype "passive"))
    )
    (net (code "63") (name "Net-(STM32F405R-PA14{slash}JTCK-SWCLK(5T))") (class "Default")
      (node (ref "STM32F405R") (pin "49") (pinfunction "PA14/JTCK-SWCLK(5T)_49") (pintype "bidirectional"))
      (node (ref "U$1") (pin "3") (pinfunction "3_3") (pintype "passive"))
    )
    (net (code "64") (name "Net-(STM32F405R-PH0{slash}OSC_IN(5T))") (class "Default")
      (node (ref "C4") (pin "1") (pinfunction "1_1") (pintype "passive"))
      (node (ref "STM32F405R") (pin "5") (pinfunction "PH0/OSC_IN(5T)_5") (pintype "bidirectional"))
      (node (ref "U$2") (pin "1") (pinfunction "P$1_1") (pintype "bidirectional"))
    )
    (net (code "65") (name "Net-(STM32F405R-PH1{slash}OSC_OUT(5T))") (class "Default")
      (node (ref "C3") (pin "1") (pinfunction "1_1") (pintype "passive"))
      (node (ref "STM32F405R") (pin "6") (pinfunction "PH1/OSC_OUT(5T)_6") (pintype "bidirectional"))
      (node (ref "U$2") (pin "3") (pinfunction "P$2_3") (pintype "bidirectional"))
    )
    (net (code "66") (name "Net-(STM32F405R-VCAP_1)") (class "Default")
      (node (ref "C1") (pin "1") (pinfunction "1_1") (pintype "passive"))
      (node (ref "STM32F405R") (pin "31") (pinfunction "VCAP_1_31") (pintype "bidirectional"))
    )
    (net (code "67") (name "Net-(STM32F405R-VCAP_2)") (class "Default")
      (node (ref "C2") (pin "1") (pinfunction "1_1") (pintype "passive"))
      (node (ref "STM32F405R") (pin "47") (pinfunction "VCAP_2_47") (pintype "bidirectional"))
    )
    (net (code "68") (name "Net-(SV1-Pad1)") (class "Default")
      (node (ref "SV1") (pin "1") (pinfunction "1_1") (pintype "passive"))
      (node (ref "U$4") (pin "1") (pinfunction "A01_1") (pintype "bidirectional"))
      (node (ref "U$4") (pin "2") (pinfunction "A01_2") (pintype "bidirectional"))
    )
    (net (code "69") (name "Net-(SV1-Pad2)") (class "Default")
      (node (ref "SV1") (pin "2") (pinfunction "2_2") (pintype "passive"))
      (node (ref "U$4") (pin "5") (pinfunction "A02_5") (pintype "bidirectional"))
      (node (ref "U$4") (pin "6") (pinfunction "A02_6") (pintype "bidirectional"))
    )
    (net (code "70") (name "Net-(SV2-Pad1)") (class "Default")
      (node (ref "SV2") (pin "1") (pinfunction "1_1") (pintype "passive"))
      (node (ref "U$4") (pin "7") (pinfunction "B02_7") (pintype "bidirectional"))
      (node (ref "U$4") (pin "8") (pinfunction "B02_8") (pintype "bidirectional"))
    )
    (net (code "71") (name "Net-(SV2-Pad2)") (class "Default")
      (node (ref "SV2") (pin "2") (pinfunction "2_2") (pintype "passive"))
      (node (ref "U$4") (pin "11") (pinfunction "BO1_11") (pintype "bidirectional"))
      (node (ref "U$4") (pin "12") (pinfunction "BO1_12") (pintype "bidirectional"))
    )
    (net (code "72") (name "unconnected-(MPU-9250-AUX_CL-Pad7)") (class "Default")
      (node (ref "MPU-9250") (pin "7") (pinfunction "AUX_CL_7") (pintype "bidirectional"))
    )
    (net (code "73") (name "unconnected-(MPU-9250-AUX_DA-Pad8)") (class "Default")
      (node (ref "MPU-9250") (pin "8") (pinfunction "AUX_DA_8") (pintype "bidirectional"))
    )
    (net (code "74") (name "unconnected-(MPU-9250-INT-Pad9)") (class "Default")
      (node (ref "MPU-9250") (pin "9") (pinfunction "INT_9") (pintype "bidirectional"))
    )
    (net (code "75") (name "unconnected-(STM32F405R-PA6{slash}ADC12_IN6(5T)-Pad22)") (class "Default")
      (node (ref "STM32F405R") (pin "22") (pinfunction "PA6/ADC12_IN6(5T)_22") (pintype "bidirectional"))
    )
    (net (code "76") (name "unconnected-(STM32F405R-PA7{slash}TIM1_CH1N{slash}ADC12_IN7(FT)-Pad23)") (class "Default")
      (node (ref "STM32F405R") (pin "23") (pinfunction "PA7/TIM1_CH1N/ADC12_IN7(FT)_23") (pintype "bidirectional"))
    )
    (net (code "77") (name "unconnected-(STM32F405R-PA12{slash}CANTX{slash}USBDP(5T)-Pad45)") (class "Default")
      (node (ref "STM32F405R") (pin "45") (pinfunction "PA12/CANTX/USBDP(5T)_45") (pintype "bidirectional"))
    )
    (net (code "78") (name "unconnected-(STM32F405R-PA15{slash}JTDI(5T)-Pad50)") (class "Default")
      (node (ref "STM32F405R") (pin "50") (pinfunction "PA15/JTDI(5T)_50") (pintype "bidirectional"))
    )
    (net (code "79") (name "unconnected-(STM32F405R-PC0{slash}ADC123_IN10(5T)-Pad8)") (class "Default")
      (node (ref "STM32F405R") (pin "8") (pinfunction "PC0/ADC123_IN10(5T)_8") (pintype "bidirectional"))
    )
    (net (code "80") (name "unconnected-(STM32F405R-PC1{slash}ADC123_IN11(5T)-Pad9)") (class "Default")
      (node (ref "STM32F405R") (pin "9") (pinfunction "PC1/ADC123_IN11(5T)_9") (pintype "bidirectional"))
    )
    (net (code "81") (name "unconnected-(STM32F405R-PC2{slash}ADC123_IN12(5T)-Pad10)") (class "Default")
      (node (ref "STM32F405R") (pin "10") (pinfunction "PC2/ADC123_IN12(5T)_10") (pintype "bidirectional"))
    )
    (net (code "82") (name "unconnected-(STM32F405R-PC3{slash}ADC123_IN13(5T)-Pad11)") (class "Default")
      (node (ref "STM32F405R") (pin "11") (pinfunction "PC3/ADC123_IN13(5T)_11") (pintype "bidirectional"))
    )
    (net (code "83") (name "unconnected-(STM32F405R-PC4{slash}ADC12_IN14-Pad24)") (class "Default")
      (node (ref "STM32F405R") (pin "24") (pinfunction "PC4/ADC12_IN14_24") (pintype "bidirectional"))
    )
    (net (code "84") (name "unconnected-(STM32F405R-PC5{slash}ADC12_IN15-Pad25)") (class "Default")
      (node (ref "STM32F405R") (pin "25") (pinfunction "PC5/ADC12_IN15_25") (pintype "bidirectional"))
    )
    (net (code "85") (name "unconnected-(STM32F405R-PC8{slash}TIM3_CH3{slash}TIM8_CH3(5T)-Pad39)") (class "Default")
      (node (ref "STM32F405R") (pin "39") (pinfunction "PC8/TIM3_CH3/TIM8_CH3(5T)_39") (pintype "bidirectional"))
    )
    (net (code "86") (name "unconnected-(STM32F405R-PC9{slash}TIM3_CH4{slash}TIM8_CH4(5T)-Pad40)") (class "Default")
      (node (ref "STM32F405R") (pin "40") (pinfunction "PC9/TIM3_CH4/TIM8_CH4(5T)_40") (pintype "bidirectional"))
    )
    (net (code "87") (name "unconnected-(STM32F405R-PC15{slash}OSC32_OUT(5T)-Pad4)") (class "Default")
      (node (ref "STM32F405R") (pin "4") (pinfunction "PC15/OSC32_OUT(5T)_4") (pintype "bidirectional"))
    )
    (net (code "88") (name "unconnected-(STM32F405R-PD2{slash}TIM3_ETR(5T)-Pad54)") (class "Default")
      (node (ref "STM32F405R") (pin "54") (pinfunction "PD2/TIM3_ETR(5T)_54") (pintype "bidirectional"))
    )
    (net (code "89") (name "unconnected-(STM32F405R-VBAT-Pad1)") (class "Default")
      (node (ref "STM32F405R") (pin "1") (pinfunction "VBAT_1") (pintype "bidirectional"))
    )
  )
)
